# Main.net
KiCad netlist of a schematic drawn in Altium Designer
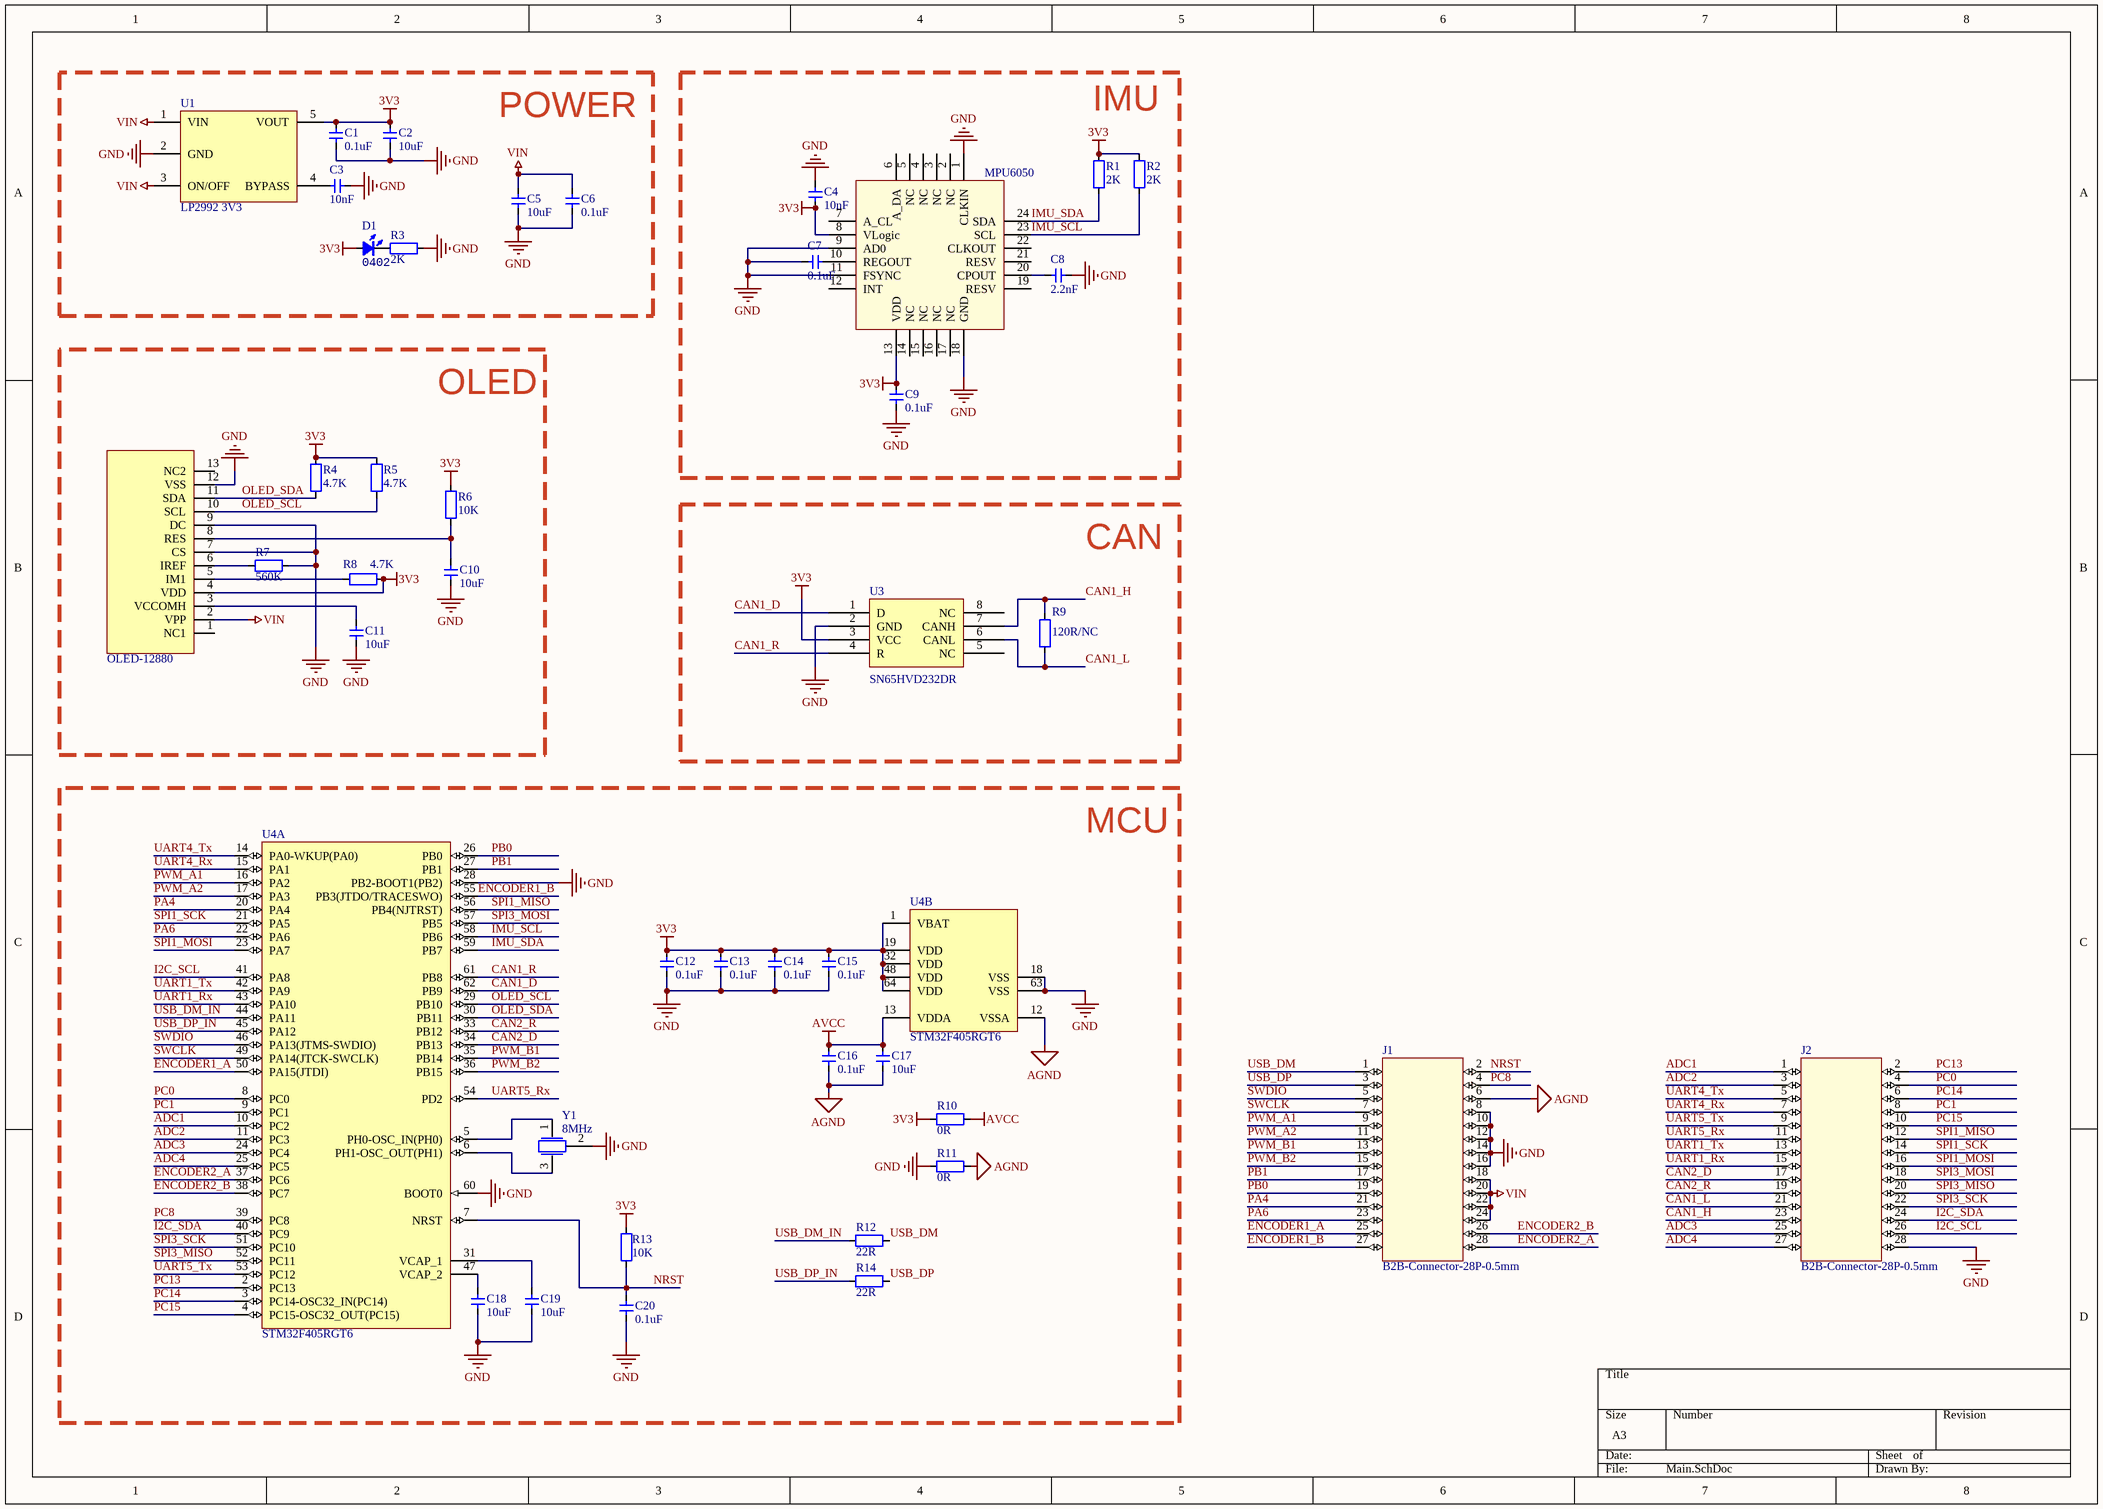
[diagram p0: Main.SchDoc]

(export (version "E")
  (design (tool "Eeschema 10.0.6"))
  (components
    (comp (ref "1")
      (value "OLED-12880")
      (footprint "OLED-12880")
      (libsource (lib "mLib") (part "OLED-12880"))
    )
    (comp (ref "C1")
      (value "0.1uF")
      (footprint "CAP_0402")
      (description "Capacitor")
      (libsource (lib "MyPcbLib") (part "电容-0402"))
    )
    (comp (ref "C2")
      (value "10uF")
      (footprint "CAP_0402")
      (description "Capacitor")
      (libsource (lib "MyPcbLib") (part "电容-0402"))
    )
    (comp (ref "C3")
      (value "10nF")
      (footprint "CAP_0402")
      (description "Capacitor")
      (libsource (lib "MyPcbLib") (part "电容-0402"))
    )
    (comp (ref "C4")
      (value "10nF")
      (footprint "CAP_0402")
      (description "Capacitor")
      (libsource (lib "MyPcbLib") (part "电容-0402"))
    )
    (comp (ref "C5")
      (value "10uF")
      (footprint "CAP_0402")
      (description "Capacitor")
      (libsource (lib "MyPcbLib") (part "电容-0402"))
    )
    (comp (ref "C6")
      (value "0.1uF")
      (footprint "CAP_0402")
      (description "Capacitor")
      (libsource (lib "MyPcbLib") (part "电容-0402"))
    )
    (comp (ref "C7")
      (value "0.1uF")
      (footprint "CAP_0402")
      (description "Capacitor")
      (libsource (lib "MyPcbLib") (part "电容-0402"))
    )
    (comp (ref "C8")
      (value "2.2nF")
      (footprint "CAP_0402")
      (description "Capacitor")
      (libsource (lib "MyPcbLib") (part "电容-0402"))
    )
    (comp (ref "C9")
      (value "0.1uF")
      (footprint "CAP_0402")
      (description "Capacitor")
      (libsource (lib "MyPcbLib") (part "电容-0402"))
    )
    (comp (ref "C10")
      (value "10uF")
      (footprint "CAP_0402")
      (description "Capacitor")
      (libsource (lib "MyPcbLib") (part "电容-0402"))
    )
    (comp (ref "C11")
      (value "10uF")
      (footprint "CAP_0402")
      (description "Capacitor")
      (libsource (lib "MyPcbLib") (part "电容-0402"))
    )
    (comp (ref "C12")
      (value "0.1uF")
      (footprint "CAP_0402")
      (description "Capacitor")
      (libsource (lib "MyPcbLib") (part "电容-0402"))
    )
    (comp (ref "C13")
      (value "0.1uF")
      (footprint "CAP_0402")
      (description "Capacitor")
      (libsource (lib "MyPcbLib") (part "电容-0402"))
    )
    (comp (ref "C14")
      (value "0.1uF")
      (footprint "CAP_0402")
      (description "Capacitor")
      (libsource (lib "MyPcbLib") (part "电容-0402"))
    )
    (comp (ref "C15")
      (value "0.1uF")
      (footprint "CAP_0402")
      (description "Capacitor")
      (libsource (lib "MyPcbLib") (part "电容-0402"))
    )
    (comp (ref "C16")
      (value "0.1uF")
      (footprint "CAP_0402")
      (description "Capacitor")
      (libsource (lib "MyPcbLib") (part "电容-0402"))
    )
    (comp (ref "C17")
      (value "10uF")
      (footprint "CAP_0402")
      (description "Capacitor")
      (libsource (lib "MyPcbLib") (part "电容-0402"))
    )
    (comp (ref "C18")
      (value "10uF")
      (footprint "CAP_0402")
      (description "Capacitor")
      (libsource (lib "MyPcbLib") (part "电容-0402"))
    )
    (comp (ref "C19")
      (value "10uF")
      (footprint "CAP_0402")
      (description "Capacitor")
      (libsource (lib "MyPcbLib") (part "电容-0402"))
    )
    (comp (ref "C20")
      (value "0.1uF")
      (footprint "CAP_0402")
      (description "Capacitor")
      (libsource (lib "MyPcbLib") (part "电容-0402"))
    )
    (comp (ref "D1")
      (value "color?")
      (footprint "LED_0402_RED")
      (description "LED")
      (fields (field (name "TYPE") "0402"))
      (libsource (lib "KitSprout") (part "LED_0402"))
    )
    (comp (ref "J1")
      (value "B2B-Connector-28P-0.5mm")
      (footprint "B2B-0.5mm-28P-M")
      (libsource (lib "MyPcbLib") (part "B2B-Connector-28P-0.5mm"))
    )
    (comp (ref "J2")
      (value "B2B-Connector-28P-0.5mm")
      (footprint "B2B-0.5mm-28P-M")
      (libsource (lib "MyPcbLib") (part "B2B-Connector-28P-0.5mm"))
    )
    (comp (ref "R1")
      (value "2K")
      (footprint "RES_0402")
      (description "Resistor")
      (libsource (lib "MyPcbLib") (part "电阻-0402"))
    )
    (comp (ref "R2")
      (value "2K")
      (footprint "RES_0402")
      (description "Resistor")
      (libsource (lib "MyPcbLib") (part "电阻-0402"))
    )
    (comp (ref "R3")
      (value "2K")
      (footprint "RES_0402")
      (description "Resistor")
      (libsource (lib "") (part "电阻-0402_1"))
    )
    (comp (ref "R4")
      (value "4.7K")
      (footprint "RES_0402")
      (description "Resistor")
      (libsource (lib "MyPcbLib") (part "电阻-0402"))
    )
    (comp (ref "R5")
      (value "4.7K")
      (footprint "RES_0402")
      (description "Resistor")
      (libsource (lib "MyPcbLib") (part "电阻-0402"))
    )
    (comp (ref "R6")
      (value "10K")
      (footprint "RES_0402")
      (description "Resistor")
      (libsource (lib "MyPcbLib") (part "电阻-0402"))
    )
    (comp (ref "R7")
      (value "560K")
      (footprint "RES_0402")
      (description "Resistor")
      (libsource (lib "") (part "电阻-0402_2"))
    )
    (comp (ref "R8")
      (value "4.7K")
      (footprint "RES_0402")
      (description "Resistor")
      (libsource (lib "") (part "电阻-0402_2"))
    )
    (comp (ref "R9")
      (value "120R/NC")
      (footprint "RES_0402")
      (description "Resistor")
      (libsource (lib "") (part "电阻-0402_3"))
    )
    (comp (ref "R10")
      (value "0R")
      (footprint "RES_0402")
      (description "Resistor")
      (libsource (lib "") (part "电阻-0402_1"))
    )
    (comp (ref "R11")
      (value "0R")
      (footprint "RES_0402")
      (description "Resistor")
      (libsource (lib "") (part "电阻-0402_1"))
    )
    (comp (ref "R12")
      (value "22R")
      (footprint "RES_0402")
      (description "Resistor")
      (libsource (lib "") (part "电阻-0402_1"))
    )
    (comp (ref "R13")
      (value "10K")
      (footprint "RES_0402")
      (description "Resistor")
      (libsource (lib "MyPcbLib") (part "电阻-0402"))
    )
    (comp (ref "R14")
      (value "22R")
      (footprint "RES_0402")
      (description "Resistor")
      (libsource (lib "") (part "电阻-0402_1"))
    )
    (comp (ref "U1")
      (value "LP2992 3V3")
      (footprint "SOT23-5")
      (description "LDO")
      (libsource (lib "MyPcbLib") (part "LP2992"))
    )
    (comp (ref "U2")
      (value "MPU6050")
      (footprint "QFN-24")
      (description "六轴传感器")
      (libsource (lib "mLib") (part "MPU6050"))
    )
    (comp (ref "U3")
      (value "SN65HVD232D")
      (footprint "SO-8")
      (fields
        (field (name "MANUFACTURER") "Texas Instruments")
        (field (name "MANUFACTURER PART NUMBER") "SN65HVD232DR")
      )
      (libsource (lib "MyPcbLib") (part "SN65HVD232D"))
    )
    (comp (ref "U4")
      (value "STM32F405RGT6")
      (footprint "LQFP-64_N")
      (fields (field (name "MANUFACTURER") "STMicroelectronics"))
      (libsource (lib "STMicroelectronics STM32 F4") (part "STM32F405RGT6"))
    )
    (comp (ref "Y1")
      (value "8MHz")
      (footprint "晶振-3P")
      (description "村田贴片")
      (libsource (lib "MyPcbLib") (part "晶振-3Pin"))
    )
  )
  (nets
    (net (code "1") (name "/ADC1") (class "Default")
      (node (ref "J2") (pin "1") (pintype "bidirectional"))
      (node (ref "U4") (pin "10") (pinfunction "PC2_10") (pintype "bidirectional"))
    )
    (net (code "2") (name "/ADC2") (class "Default")
      (node (ref "J2") (pin "3") (pintype "bidirectional"))
      (node (ref "U4") (pin "11") (pinfunction "PC3_11") (pintype "bidirectional"))
    )
    (net (code "3") (name "/ADC3") (class "Default")
      (node (ref "J2") (pin "25") (pintype "bidirectional"))
      (node (ref "U4") (pin "24") (pinfunction "PC4_24") (pintype "bidirectional"))
    )
    (net (code "4") (name "/ADC4") (class "Default")
      (node (ref "J2") (pin "27") (pintype "bidirectional"))
      (node (ref "U4") (pin "25") (pinfunction "PC5_25") (pintype "bidirectional"))
    )
    (net (code "5") (name "/CAN1_D") (class "Default")
      (node (ref "U3") (pin "1") (pinfunction "D_1") (pintype "passive"))
      (node (ref "U4") (pin "62") (pinfunction "PB9_62") (pintype "bidirectional"))
    )
    (net (code "6") (name "/CAN1_H") (class "Default")
      (node (ref "J2") (pin "23") (pintype "bidirectional"))
      (node (ref "R9") (pin "1") (pinfunction "1_1") (pintype "passive"))
      (node (ref "U3") (pin "7") (pinfunction "CANH_7") (pintype "passive"))
    )
    (net (code "7") (name "/CAN1_L") (class "Default")
      (node (ref "J2") (pin "21") (pintype "bidirectional"))
      (node (ref "R9") (pin "2") (pinfunction "2_2") (pintype "passive"))
      (node (ref "U3") (pin "6") (pinfunction "CANL_6") (pintype "passive"))
    )
    (net (code "8") (name "/CAN1_R") (class "Default")
      (node (ref "U3") (pin "4") (pinfunction "R_4") (pintype "passive"))
      (node (ref "U4") (pin "61") (pinfunction "PB8_61") (pintype "bidirectional"))
    )
    (net (code "9") (name "/CAN2_D") (class "Default")
      (node (ref "J2") (pin "17") (pintype "bidirectional"))
      (node (ref "U4") (pin "34") (pinfunction "PB13_34") (pintype "bidirectional"))
    )
    (net (code "10") (name "/CAN2_R") (class "Default")
      (node (ref "J2") (pin "19") (pintype "bidirectional"))
      (node (ref "U4") (pin "33") (pinfunction "PB12_33") (pintype "bidirectional"))
    )
    (net (code "11") (name "/ENCODER1_A") (class "Default")
      (node (ref "J1") (pin "25") (pintype "bidirectional"))
      (node (ref "U4") (pin "50") (pinfunction "PA15(JTDI)_50") (pintype "bidirectional"))
    )
    (net (code "12") (name "/ENCODER1_B") (class "Default")
      (node (ref "J1") (pin "27") (pintype "bidirectional"))
      (node (ref "U4") (pin "55") (pinfunction "PB3(JTDO/TRACESWO)_55") (pintype "bidirectional"))
    )
    (net (code "13") (name "/ENCODER2_A") (class "Default")
      (node (ref "J1") (pin "28") (pintype "bidirectional"))
      (node (ref "U4") (pin "37") (pinfunction "PC6_37") (pintype "bidirectional"))
    )
    (net (code "14") (name "/ENCODER2_B") (class "Default")
      (node (ref "J1") (pin "26") (pintype "bidirectional"))
      (node (ref "U4") (pin "38") (pinfunction "PC7_38") (pintype "bidirectional"))
    )
    (net (code "15") (name "/I2C_SCL") (class "Default")
      (node (ref "J2") (pin "26") (pintype "bidirectional"))
      (node (ref "U4") (pin "41") (pinfunction "PA8_41") (pintype "bidirectional"))
    )
    (net (code "16") (name "/I2C_SDA") (class "Default")
      (node (ref "J2") (pin "24") (pintype "bidirectional"))
      (node (ref "U4") (pin "40") (pinfunction "PC9_40") (pintype "bidirectional"))
    )
    (net (code "17") (name "/IMU_SCL") (class "Default")
      (node (ref "R2") (pin "1") (pinfunction "1_1") (pintype "passive"))
      (node (ref "U2") (pin "23") (pinfunction "SCL_23") (pintype "passive"))
      (node (ref "U4") (pin "58") (pinfunction "PB6_58") (pintype "bidirectional"))
    )
    (net (code "18") (name "/IMU_SDA") (class "Default")
      (node (ref "R1") (pin "1") (pinfunction "1_1") (pintype "passive"))
      (node (ref "U2") (pin "24") (pinfunction "SDA_24") (pintype "passive"))
      (node (ref "U4") (pin "59") (pinfunction "PB7_59") (pintype "bidirectional"))
    )
    (net (code "19") (name "/NRST") (class "Default")
      (node (ref "C20") (pin "2") (pinfunction "2_2") (pintype "passive"))
      (node (ref "J1") (pin "2") (pintype "bidirectional"))
      (node (ref "R13") (pin "1") (pinfunction "1_1") (pintype "passive"))
      (node (ref "U4") (pin "7") (pinfunction "NRST_7") (pintype "bidirectional"))
    )
    (net (code "20") (name "/OLED_SCL") (class "Default")
      (node (ref "1") (pin "10") (pinfunction "SCL_10") (pintype "passive"))
      (node (ref "R5") (pin "1") (pinfunction "1_1") (pintype "passive"))
      (node (ref "U4") (pin "29") (pinfunction "PB10_29") (pintype "bidirectional"))
    )
    (net (code "21") (name "/OLED_SDA") (class "Default")
      (node (ref "1") (pin "11") (pinfunction "SDA_11") (pintype "passive"))
      (node (ref "R4") (pin "1") (pinfunction "1_1") (pintype "passive"))
      (node (ref "U4") (pin "30") (pinfunction "PB11_30") (pintype "bidirectional"))
    )
    (net (code "22") (name "/PA4") (class "Default")
      (node (ref "J1") (pin "21") (pintype "bidirectional"))
      (node (ref "U4") (pin "20") (pinfunction "PA4_20") (pintype "bidirectional"))
    )
    (net (code "23") (name "/PA6") (class "Default")
      (node (ref "J1") (pin "23") (pintype "bidirectional"))
      (node (ref "U4") (pin "22") (pinfunction "PA6_22") (pintype "bidirectional"))
    )
    (net (code "24") (name "/PB0") (class "Default")
      (node (ref "J1") (pin "19") (pintype "bidirectional"))
      (node (ref "U4") (pin "26") (pinfunction "PB0_26") (pintype "bidirectional"))
    )
    (net (code "25") (name "/PB1") (class "Default")
      (node (ref "J1") (pin "17") (pintype "bidirectional"))
      (node (ref "U4") (pin "27") (pinfunction "PB1_27") (pintype "bidirectional"))
    )
    (net (code "26") (name "/PC0") (class "Default")
      (node (ref "J2") (pin "4") (pintype "bidirectional"))
      (node (ref "U4") (pin "8") (pinfunction "PC0_8") (pintype "bidirectional"))
    )
    (net (code "27") (name "/PC1") (class "Default")
      (node (ref "J2") (pin "8") (pintype "bidirectional"))
      (node (ref "U4") (pin "9") (pinfunction "PC1_9") (pintype "bidirectional"))
    )
    (net (code "28") (name "/PC8") (class "Default")
      (node (ref "J1") (pin "4") (pintype "bidirectional"))
      (node (ref "U4") (pin "39") (pinfunction "PC8_39") (pintype "bidirectional"))
    )
    (net (code "29") (name "/PC13") (class "Default")
      (node (ref "J2") (pin "2") (pintype "bidirectional"))
      (node (ref "U4") (pin "2") (pinfunction "PC13_2") (pintype "bidirectional"))
    )
    (net (code "30") (name "/PC14") (class "Default")
      (node (ref "J2") (pin "6") (pintype "bidirectional"))
      (node (ref "U4") (pin "3") (pinfunction "PC14-OSC32_IN(PC14)_3") (pintype "bidirectional"))
    )
    (net (code "31") (name "/PC15") (class "Default")
      (node (ref "J2") (pin "10") (pintype "bidirectional"))
      (node (ref "U4") (pin "4") (pinfunction "PC15-OSC32_OUT(PC15)_4") (pintype "bidirectional"))
    )
    (net (code "32") (name "/PWM_A1") (class "Default")
      (node (ref "J1") (pin "9") (pintype "bidirectional"))
      (node (ref "U4") (pin "16") (pinfunction "PA2_16") (pintype "bidirectional"))
    )
    (net (code "33") (name "/PWM_A2") (class "Default")
      (node (ref "J1") (pin "11") (pintype "bidirectional"))
      (node (ref "U4") (pin "17") (pinfunction "PA3_17") (pintype "bidirectional"))
    )
    (net (code "34") (name "/PWM_B1") (class "Default")
      (node (ref "J1") (pin "13") (pintype "bidirectional"))
      (node (ref "U4") (pin "35") (pinfunction "PB14_35") (pintype "bidirectional"))
    )
    (net (code "35") (name "/PWM_B2") (class "Default")
      (node (ref "J1") (pin "15") (pintype "bidirectional"))
      (node (ref "U4") (pin "36") (pinfunction "PB15_36") (pintype "bidirectional"))
    )
    (net (code "36") (name "/SPI1_MISO") (class "Default")
      (node (ref "J2") (pin "12") (pintype "bidirectional"))
      (node (ref "U4") (pin "56") (pinfunction "PB4(NJTRST)_56") (pintype "bidirectional"))
    )
    (net (code "37") (name "/SPI1_MOSI") (class "Default")
      (node (ref "J2") (pin "16") (pintype "bidirectional"))
      (node (ref "U4") (pin "23") (pinfunction "PA7_23") (pintype "bidirectional"))
    )
    (net (code "38") (name "/SPI1_SCK") (class "Default")
      (node (ref "J2") (pin "14") (pintype "bidirectional"))
      (node (ref "U4") (pin "21") (pinfunction "PA5_21") (pintype "bidirectional"))
    )
    (net (code "39") (name "/SPI3_MISO") (class "Default")
      (node (ref "J2") (pin "20") (pintype "bidirectional"))
      (node (ref "U4") (pin "52") (pinfunction "PC11_52") (pintype "bidirectional"))
    )
    (net (code "40") (name "/SPI3_MOSI") (class "Default")
      (node (ref "J2") (pin "18") (pintype "bidirectional"))
      (node (ref "U4") (pin "57") (pinfunction "PB5_57") (pintype "bidirectional"))
    )
    (net (code "41") (name "/SPI3_SCK") (class "Default")
      (node (ref "J2") (pin "22") (pintype "bidirectional"))
      (node (ref "U4") (pin "51") (pinfunction "PC10_51") (pintype "bidirectional"))
    )
    (net (code "42") (name "/SWCLK") (class "Default")
      (node (ref "J1") (pin "7") (pintype "bidirectional"))
      (node (ref "U4") (pin "49") (pinfunction "PA14(JTCK-SWCLK)_49") (pintype "bidirectional"))
    )
    (net (code "43") (name "/SWDIO") (class "Default")
      (node (ref "J1") (pin "5") (pintype "bidirectional"))
      (node (ref "U4") (pin "46") (pinfunction "PA13(JTMS-SWDIO)_46") (pintype "bidirectional"))
    )
    (net (code "44") (name "/UART1_Rx") (class "Default")
      (node (ref "J2") (pin "15") (pintype "bidirectional"))
      (node (ref "U4") (pin "43") (pinfunction "PA10_43") (pintype "bidirectional"))
    )
    (net (code "45") (name "/UART1_Tx") (class "Default")
      (node (ref "J2") (pin "13") (pintype "bidirectional"))
      (node (ref "U4") (pin "42") (pinfunction "PA9_42") (pintype "bidirectional"))
    )
    (net (code "46") (name "/UART4_Rx") (class "Default")
      (node (ref "J2") (pin "7") (pintype "bidirectional"))
      (node (ref "U4") (pin "15") (pinfunction "PA1_15") (pintype "bidirectional"))
    )
    (net (code "47") (name "/UART4_Tx") (class "Default")
      (node (ref "J2") (pin "5") (pintype "bidirectional"))
      (node (ref "U4") (pin "14") (pinfunction "PA0-WKUP(PA0)_14") (pintype "bidirectional"))
    )
    (net (code "48") (name "/UART5_Rx") (class "Default")
      (node (ref "J2") (pin "11") (pintype "bidirectional"))
      (node (ref "U4") (pin "54") (pinfunction "PD2_54") (pintype "bidirectional"))
    )
    (net (code "49") (name "/UART5_Tx") (class "Default")
      (node (ref "J2") (pin "9") (pintype "bidirectional"))
      (node (ref "U4") (pin "53") (pinfunction "PC12_53") (pintype "bidirectional"))
    )
    (net (code "50") (name "/USB_DM") (class "Default")
      (node (ref "J1") (pin "1") (pintype "bidirectional"))
      (node (ref "R12") (pin "1") (pinfunction "1_1") (pintype "passive"))
    )
    (net (code "51") (name "/USB_DM_IN") (class "Default")
      (node (ref "R12") (pin "2") (pinfunction "2_2") (pintype "passive"))
      (node (ref "U4") (pin "44") (pinfunction "PA11_44") (pintype "bidirectional"))
    )
    (net (code "52") (name "/USB_DP") (class "Default")
      (node (ref "J1") (pin "3") (pintype "bidirectional"))
      (node (ref "R14") (pin "1") (pinfunction "1_1") (pintype "passive"))
    )
    (net (code "53") (name "/USB_DP_IN") (class "Default")
      (node (ref "R14") (pin "2") (pinfunction "2_2") (pintype "passive"))
      (node (ref "U4") (pin "45") (pinfunction "PA12_45") (pintype "bidirectional"))
    )
    (net (code "54") (name "3V3") (class "Default")
      (node (ref "1") (pin "4") (pinfunction "VDD_4") (pintype "passive"))
      (node (ref "C1") (pin "2") (pinfunction "2_2") (pintype "passive"))
      (node (ref "C12") (pin "2") (pinfunction "2_2") (pintype "passive"))
      (node (ref "C13") (pin "2") (pinfunction "2_2") (pintype "passive"))
      (node (ref "C14") (pin "2") (pinfunction "2_2") (pintype "passive"))
      (node (ref "C15") (pin "2") (pinfunction "2_2") (pintype "passive"))
      (node (ref "C2") (pin "2") (pinfunction "2_2") (pintype "passive"))
      (node (ref "C4") (pin "1") (pinfunction "1_1") (pintype "passive"))
      (node (ref "C9") (pin "2") (pinfunction "2_2") (pintype "passive"))
      (node (ref "D1") (pin "1") (pinfunction "A_1") (pintype "passive"))
      (node (ref "R1") (pin "2") (pinfunction "2_2") (pintype "passive"))
      (node (ref "R10") (pin "2") (pinfunction "2_2") (pintype "passive"))
      (node (ref "R13") (pin "2") (pinfunction "2_2") (pintype "passive"))
      (node (ref "R2") (pin "2") (pinfunction "2_2") (pintype "passive"))
      (node (ref "R4") (pin "2") (pinfunction "2_2") (pintype "passive"))
      (node (ref "R5") (pin "2") (pinfunction "2_2") (pintype "passive"))
      (node (ref "R6") (pin "2") (pinfunction "2_2") (pintype "passive"))
      (node (ref "R8") (pin "2") (pinfunction "2_2") (pintype "passive"))
      (node (ref "U1") (pin "5") (pinfunction "VOUT_5") (pintype "passive"))
      (node (ref "U2") (pin "13") (pinfunction "VDD_13") (pintype "passive"))
      (node (ref "U2") (pin "8") (pinfunction "VLogic_8") (pintype "passive"))
      (node (ref "U3") (pin "3") (pinfunction "VCC_3") (pintype "passive"))
      (node (ref "U4") (pin "1") (pinfunction "VBAT_1") (pintype "power_in"))
      (node (ref "U4") (pin "19") (pinfunction "VDD_19") (pintype "power_in"))
      (node (ref "U4") (pin "32") (pinfunction "VDD_32") (pintype "power_in"))
      (node (ref "U4") (pin "48") (pinfunction "VDD_48") (pintype "power_in"))
      (node (ref "U4") (pin "64") (pinfunction "VDD_64") (pintype "power_in"))
    )
    (net (code "55") (name "AGND") (class "Default")
      (node (ref "C16") (pin "1") (pinfunction "1_1") (pintype "passive"))
      (node (ref "C17") (pin "1") (pinfunction "1_1") (pintype "passive"))
      (node (ref "J1") (pin "6") (pintype "bidirectional"))
      (node (ref "R11") (pin "1") (pinfunction "1_1") (pintype "passive"))
      (node (ref "U4") (pin "12") (pinfunction "VSSA_12") (pintype "power_in"))
    )
    (net (code "56") (name "AVCC") (class "Default")
      (node (ref "C16") (pin "2") (pinfunction "2_2") (pintype "passive"))
      (node (ref "C17") (pin "2") (pinfunction "2_2") (pintype "passive"))
      (node (ref "R10") (pin "1") (pinfunction "1_1") (pintype "passive"))
      (node (ref "U4") (pin "13") (pinfunction "VDDA_13") (pintype "power_in"))
    )
    (net (code "57") (name "GND") (class "Default")
      (node (ref "1") (pin "12") (pinfunction "VSS_12") (pintype "passive"))
      (node (ref "1") (pin "7") (pinfunction "CS_7") (pintype "passive"))
      (node (ref "1") (pin "9") (pinfunction "DC_9") (pintype "passive"))
      (node (ref "C1") (pin "1") (pinfunction "1_1") (pintype "passive"))
      (node (ref "C10") (pin "1") (pinfunction "1_1") (pintype "passive"))
      (node (ref "C11") (pin "1") (pinfunction "1_1") (pintype "passive"))
      (node (ref "C12") (pin "1") (pinfunction "1_1") (pintype "passive"))
      (node (ref "C13") (pin "1") (pinfunction "1_1") (pintype "passive"))
      (node (ref "C14") (pin "1") (pinfunction "1_1") (pintype "passive"))
      (node (ref "C15") (pin "1") (pinfunction "1_1") (pintype "passive"))
      (node (ref "C18") (pin "1") (pinfunction "1_1") (pintype "passive"))
      (node (ref "C19") (pin "1") (pinfunction "1_1") (pintype "passive"))
      (node (ref "C2") (pin "1") (pinfunction "1_1") (pintype "passive"))
      (node (ref "C20") (pin "1") (pinfunction "1_1") (pintype "passive"))
      (node (ref "C3") (pin "1") (pinfunction "1_1") (pintype "passive"))
      (node (ref "C4") (pin "2") (pinfunction "2_2") (pintype "passive"))
      (node (ref "C5") (pin "1") (pinfunction "1_1") (pintype "passive"))
      (node (ref "C6") (pin "1") (pinfunction "1_1") (pintype "passive"))
      (node (ref "C7") (pin "2") (pinfunction "2_2") (pintype "passive"))
      (node (ref "C8") (pin "1") (pinfunction "1_1") (pintype "passive"))
      (node (ref "C9") (pin "1") (pinfunction "1_1") (pintype "passive"))
      (node (ref "J1") (pin "10") (pintype "bidirectional"))
      (node (ref "J1") (pin "12") (pintype "bidirectional"))
      (node (ref "J1") (pin "14") (pintype "bidirectional"))
      (node (ref "J1") (pin "16") (pintype "bidirectional"))
      (node (ref "J1") (pin "8") (pintype "bidirectional"))
      (node (ref "J2") (pin "28") (pintype "bidirectional"))
      (node (ref "R11") (pin "2") (pinfunction "2_2") (pintype "passive"))
      (node (ref "R3") (pin "1") (pinfunction "1_1") (pintype "passive"))
      (node (ref "R7") (pin "2") (pinfunction "2_2") (pintype "passive"))
      (node (ref "U1") (pin "2") (pinfunction "GND_2") (pintype "passive"))
      (node (ref "U2") (pin "1") (pinfunction "CLKIN_1") (pintype "passive"))
      (node (ref "U2") (pin "11") (pinfunction "FSYNC_11") (pintype "passive"))
      (node (ref "U2") (pin "18") (pinfunction "GND_18") (pintype "passive"))
      (node (ref "U2") (pin "9") (pinfunction "AD0_9") (pintype "passive"))
      (node (ref "U3") (pin "2") (pinfunction "GND_2") (pintype "passive"))
      (node (ref "U4") (pin "18") (pinfunction "VSS_18") (pintype "power_in"))
      (node (ref "U4") (pin "28") (pinfunction "PB2-BOOT1(PB2)_28") (pintype "bidirectional"))
      (node (ref "U4") (pin "60") (pinfunction "BOOT0_60") (pintype "input"))
      (node (ref "U4") (pin "63") (pinfunction "VSS_63") (pintype "power_in"))
      (node (ref "Y1") (pin "2") (pinfunction "2_2") (pintype "passive"))
    )
    (net (code "58") (name "Net-(1-IM1)") (class "Default")
      (node (ref "1") (pin "5") (pinfunction "IM1_5") (pintype "passive"))
      (node (ref "R8") (pin "1") (pinfunction "1_1") (pintype "passive"))
    )
    (net (code "59") (name "Net-(1-IREF)") (class "Default")
      (node (ref "1") (pin "6") (pinfunction "IREF_6") (pintype "passive"))
      (node (ref "R7") (pin "1") (pinfunction "1_1") (pintype "passive"))
    )
    (net (code "60") (name "Net-(1-RES)") (class "Default")
      (node (ref "1") (pin "8") (pinfunction "RES_8") (pintype "passive"))
      (node (ref "C10") (pin "2") (pinfunction "2_2") (pintype "passive"))
      (node (ref "R6") (pin "1") (pinfunction "1_1") (pintype "passive"))
    )
    (net (code "61") (name "Net-(1-VCCOMH)") (class "Default")
      (node (ref "1") (pin "3") (pinfunction "VCCOMH_3") (pintype "passive"))
      (node (ref "C11") (pin "2") (pinfunction "2_2") (pintype "passive"))
    )
    (net (code "62") (name "Net-(D1-K)") (class "Default")
      (node (ref "D1") (pin "2") (pinfunction "K_2") (pintype "passive"))
      (node (ref "R3") (pin "2") (pinfunction "2_2") (pintype "passive"))
    )
    (net (code "63") (name "Net-(U1-BYPASS)") (class "Default")
      (node (ref "C3") (pin "2") (pinfunction "2_2") (pintype "passive"))
      (node (ref "U1") (pin "4") (pinfunction "BYPASS_4") (pintype "passive"))
    )
    (net (code "64") (name "Net-(U2-CPOUT)") (class "Default")
      (node (ref "C8") (pin "2") (pinfunction "2_2") (pintype "passive"))
      (node (ref "U2") (pin "20") (pinfunction "CPOUT_20") (pintype "passive"))
    )
    (net (code "65") (name "Net-(U2-REGOUT)") (class "Default")
      (node (ref "C7") (pin "1") (pinfunction "1_1") (pintype "passive"))
      (node (ref "U2") (pin "10") (pinfunction "REGOUT_10") (pintype "passive"))
    )
    (net (code "66") (name "Net-(U4A-PH0-OSC_IN(PH0))") (class "Default")
      (node (ref "U4") (pin "5") (pinfunction "PH0-OSC_IN(PH0)_5") (pintype "bidirectional"))
      (node (ref "Y1") (pin "1") (pinfunction "1_1") (pintype "passive"))
    )
    (net (code "67") (name "Net-(U4A-PH1-OSC_OUT(PH1))") (class "Default")
      (node (ref "U4") (pin "6") (pinfunction "PH1-OSC_OUT(PH1)_6") (pintype "bidirectional"))
      (node (ref "Y1") (pin "3") (pinfunction "3_3") (pintype "passive"))
    )
    (net (code "68") (name "Net-(U4A-VCAP_1)") (class "Default")
      (node (ref "C19") (pin "2") (pinfunction "2_2") (pintype "passive"))
      (node (ref "U4") (pin "31") (pinfunction "VCAP_1_31") (pintype "power_in"))
    )
    (net (code "69") (name "Net-(U4A-VCAP_2)") (class "Default")
      (node (ref "C18") (pin "2") (pinfunction "2_2") (pintype "passive"))
      (node (ref "U4") (pin "47") (pinfunction "VCAP_2_47") (pintype "power_in"))
    )
    (net (code "70") (name "VIN") (class "Default")
      (node (ref "1") (pin "2") (pinfunction "VPP_2") (pintype "passive"))
      (node (ref "C5") (pin "2") (pinfunction "2_2") (pintype "passive"))
      (node (ref "C6") (pin "2") (pinfunction "2_2") (pintype "passive"))
      (node (ref "J1") (pin "18") (pintype "bidirectional"))
      (node (ref "J1") (pin "20") (pintype "bidirectional"))
      (node (ref "J1") (pin "22") (pintype "bidirectional"))
      (node (ref "J1") (pin "24") (pintype "bidirectional"))
      (node (ref "U1") (pin "1") (pinfunction "VIN_1") (pintype "passive"))
      (node (ref "U1") (pin "3") (pinfunction "ON/OFF_3") (pintype "passive"))
    )
    (net (code "71") (name "unconnected-(1-NC1-Pad1)") (class "Default")
      (node (ref "1") (pin "1") (pinfunction "NC1_1") (pintype "passive"))
    )
    (net (code "72") (name "unconnected-(1-NC2-Pad13)") (class "Default")
      (node (ref "1") (pin "13") (pinfunction "NC2_13") (pintype "passive"))
    )
    (net (code "73") (name "unconnected-(U2-A_CL-Pad7)") (class "Default")
      (node (ref "U2") (pin "7") (pinfunction "A_CL_7") (pintype "passive"))
    )
    (net (code "74") (name "unconnected-(U2-A_DA-Pad6)") (class "Default")
      (node (ref "U2") (pin "6") (pinfunction "A_DA_6") (pintype "passive"))
    )
    (net (code "75") (name "unconnected-(U2-CLKOUT-Pad22)") (class "Default")
      (node (ref "U2") (pin "22") (pinfunction "CLKOUT_22") (pintype "passive"))
    )
    (net (code "76") (name "unconnected-(U2-INT-Pad12)") (class "Default")
      (node (ref "U2") (pin "12") (pinfunction "INT_12") (pintype "passive"))
    )
    (net (code "77") (name "unconnected-(U2-NC-Pad2)") (class "Default")
      (node (ref "U2") (pin "2") (pinfunction "NC_2") (pintype "passive"))
    )
    (net (code "78") (name "unconnected-(U2-NC-Pad3)") (class "Default")
      (node (ref "U2") (pin "3") (pinfunction "NC_3") (pintype "passive"))
    )
    (net (code "79") (name "unconnected-(U2-NC-Pad4)") (class "Default")
      (node (ref "U2") (pin "4") (pinfunction "NC_4") (pintype "passive"))
    )
    (net (code "80") (name "unconnected-(U2-NC-Pad5)") (class "Default")
      (node (ref "U2") (pin "5") (pinfunction "NC_5") (pintype "passive"))
    )
    (net (code "81") (name "unconnected-(U2-NC-Pad14)") (class "Default")
      (node (ref "U2") (pin "14") (pinfunction "NC_14") (pintype "passive"))
    )
    (net (code "82") (name "unconnected-(U2-NC-Pad15)") (class "Default")
      (node (ref "U2") (pin "15") (pinfunction "NC_15") (pintype "passive"))
    )
    (net (code "83") (name "unconnected-(U2-NC-Pad16)") (class "Default")
      (node (ref "U2") (pin "16") (pinfunction "NC_16") (pintype "passive"))
    )
    (net (code "84") (name "unconnected-(U2-NC-Pad17)") (class "Default")
      (node (ref "U2") (pin "17") (pinfunction "NC_17") (pintype "passive"))
    )
    (net (code "85") (name "unconnected-(U2-RESV-Pad19)") (class "Default")
      (node (ref "U2") (pin "19") (pinfunction "RESV_19") (pintype "passive"))
    )
    (net (code "86") (name "unconnected-(U2-RESV-Pad21)") (class "Default")
      (node (ref "U2") (pin "21") (pinfunction "RESV_21") (pintype "passive"))
    )
    (net (code "87") (name "unconnected-(U3-NC-Pad5)") (class "Default")
      (node (ref "U3") (pin "5") (pinfunction "NC_5") (pintype "passive"))
    )
    (net (code "88") (name "unconnected-(U3-NC-Pad8)") (class "Default")
      (node (ref "U3") (pin "8") (pinfunction "NC_8") (pintype "passive"))
    )
  )
)
